# mono_stereo_mixer.net
KiCad netlist of a schematic drawn in EAGLE
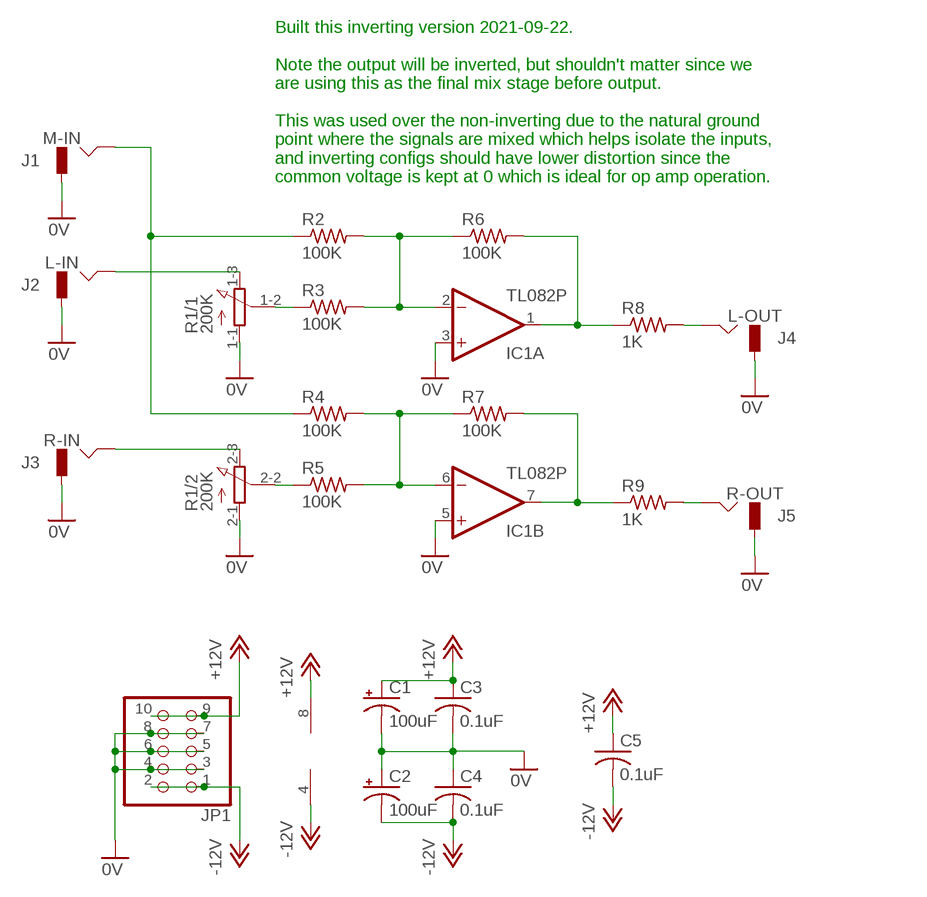
[diagram p0: schematic, sheet 1]

(export (version "E")
  (design (tool "Eeschema 10.0.6"))
  (components
    (comp (ref "C1")
      (value "100uF")
      (footprint "eagle-import:E2-5")
      (libsource (lib "eagle-import") (part "CPOL-USE2-5"))
    )
    (comp (ref "C2")
      (value "100uF")
      (footprint "eagle-import:E2-5")
      (libsource (lib "eagle-import") (part "CPOL-USE2-5"))
    )
    (comp (ref "C3")
      (value "0.1uF")
      (footprint "eagle-import:C025-024X044")
      (libsource (lib "eagle-import") (part "C-US025-024X044"))
    )
    (comp (ref "C4")
      (value "0.1uF")
      (footprint "eagle-import:C025-024X044")
      (libsource (lib "eagle-import") (part "C-US025-024X044"))
    )
    (comp (ref "C5")
      (value "0.1uF")
      (footprint "eagle-import:C025-024X044")
      (libsource (lib "eagle-import") (part "C-US025-024X044"))
    )
    (comp (ref "IC1")
      (value "TL082P")
      (footprint "eagle-import:DIL08")
      (libsource (lib "eagle-import") (part "TL082P"))
    )
    (comp (ref "J1")
      (value "M-IN")
      (footprint "eagle-import:JACK-M")
      (libsource (lib "eagle-import") (part "JACK-M"))
    )
    (comp (ref "J2")
      (value "L-IN")
      (footprint "eagle-import:JACK-M")
      (libsource (lib "eagle-import") (part "JACK-M"))
    )
    (comp (ref "J3")
      (value "R-IN")
      (footprint "eagle-import:JACK-M")
      (libsource (lib "eagle-import") (part "JACK-M"))
    )
    (comp (ref "J4")
      (value "L-OUT")
      (footprint "eagle-import:JACK-M")
      (libsource (lib "eagle-import") (part "JACK-M"))
    )
    (comp (ref "J5")
      (value "R-OUT")
      (footprint "eagle-import:JACK-M")
      (libsource (lib "eagle-import") (part "JACK-M"))
    )
    (comp (ref "JP1")
      (value "PINHD-2X5")
      (footprint "eagle-import:2X05")
      (libsource (lib "eagle-import") (part "PINHD-2X5"))
    )
    (comp (ref "R1")
      (value "200K")
      (footprint "eagle-import:3RP_1610G")
      (libsource (lib "eagle-import") (part "3RP/1610G"))
    )
    (comp (ref "R2")
      (value "100K")
      (footprint "eagle-import:0204_5")
      (libsource (lib "eagle-import") (part "R-US_0204/5"))
    )
    (comp (ref "R3")
      (value "100K")
      (footprint "eagle-import:0204_5")
      (libsource (lib "eagle-import") (part "R-US_0204/5"))
    )
    (comp (ref "R4")
      (value "100K")
      (footprint "eagle-import:0204_5")
      (libsource (lib "eagle-import") (part "R-US_0204/5"))
    )
    (comp (ref "R5")
      (value "100K")
      (footprint "eagle-import:0204_5")
      (libsource (lib "eagle-import") (part "R-US_0204/5"))
    )
    (comp (ref "R6")
      (value "100K")
      (footprint "eagle-import:0204_5")
      (libsource (lib "eagle-import") (part "R-US_0204/5"))
    )
    (comp (ref "R7")
      (value "100K")
      (footprint "eagle-import:0204_5")
      (libsource (lib "eagle-import") (part "R-US_0204/5"))
    )
    (comp (ref "R8")
      (value "1K")
      (footprint "eagle-import:0204_5")
      (libsource (lib "eagle-import") (part "R-US_0204/5"))
    )
    (comp (ref "R9")
      (value "1K")
      (footprint "eagle-import:0204_5")
      (libsource (lib "eagle-import") (part "R-US_0204/5"))
    )
  )
  (nets
    (net (code "1") (name "+12V") (class "Default")
      (node (ref "C1") (pin "+") (pinfunction "+_+") (pintype "passive"))
      (node (ref "C3") (pin "1") (pinfunction "1_1") (pintype "passive"))
      (node (ref "C5") (pin "1") (pinfunction "1_1") (pintype "passive"))
      (node (ref "IC1") (pin "8") (pinfunction "V+_8") (pintype "power_in"))
      (node (ref "JP1") (pin "10") (pinfunction "10_10") (pintype "passive"))
      (node (ref "JP1") (pin "9") (pinfunction "9_9") (pintype "passive"))
    )
    (net (code "2") (name "-12V") (class "Default")
      (node (ref "C2") (pin "-") (pinfunction "-_-") (pintype "passive"))
      (node (ref "C4") (pin "2") (pinfunction "2_2") (pintype "passive"))
      (node (ref "C5") (pin "2") (pinfunction "2_2") (pintype "passive"))
      (node (ref "IC1") (pin "4") (pinfunction "V-_4") (pintype "power_in"))
      (node (ref "JP1") (pin "1") (pinfunction "1_1") (pintype "passive"))
      (node (ref "JP1") (pin "2") (pinfunction "2_2") (pintype "passive"))
    )
    (net (code "3") (name "0V") (class "Default")
      (node (ref "C1") (pin "-") (pinfunction "-_-") (pintype "passive"))
      (node (ref "C2") (pin "+") (pinfunction "+_+") (pintype "passive"))
      (node (ref "C3") (pin "2") (pinfunction "2_2") (pintype "passive"))
      (node (ref "C4") (pin "1") (pinfunction "1_1") (pintype "passive"))
      (node (ref "IC1") (pin "3") (pinfunction "+IN_3") (pintype "input"))
      (node (ref "IC1") (pin "5") (pinfunction "+IN_5") (pintype "input"))
      (node (ref "J1") (pin "GND") (pinfunction "GND_GND") (pintype "bidirectional"))
      (node (ref "J2") (pin "GND") (pinfunction "GND_GND") (pintype "bidirectional"))
      (node (ref "J3") (pin "GND") (pinfunction "GND_GND") (pintype "bidirectional"))
      (node (ref "J4") (pin "GND") (pinfunction "GND_GND") (pintype "bidirectional"))
      (node (ref "J5") (pin "GND") (pinfunction "GND_GND") (pintype "bidirectional"))
      (node (ref "JP1") (pin "3") (pinfunction "3_3") (pintype "passive"))
      (node (ref "JP1") (pin "4") (pinfunction "4_4") (pintype "passive"))
      (node (ref "JP1") (pin "5") (pinfunction "5_5") (pintype "passive"))
      (node (ref "JP1") (pin "6") (pinfunction "6_6") (pintype "passive"))
      (node (ref "JP1") (pin "7") (pinfunction "7_7") (pintype "passive"))
      (node (ref "JP1") (pin "8") (pinfunction "8_8") (pintype "passive"))
      (node (ref "R1") (pin "1-1") (pinfunction "A_1-1") (pintype "passive"))
      (node (ref "R1") (pin "2-1") (pinfunction "A_2-1") (pintype "passive"))
    )
    (net (code "4") (name "Net-(IC1A--IN)") (class "Default")
      (node (ref "IC1") (pin "2") (pinfunction "-IN_2") (pintype "input"))
      (node (ref "R2") (pin "2") (pinfunction "2_2") (pintype "passive"))
      (node (ref "R3") (pin "2") (pinfunction "2_2") (pintype "passive"))
      (node (ref "R6") (pin "1") (pinfunction "1_1") (pintype "passive"))
    )
    (net (code "5") (name "Net-(IC1A-OUT)") (class "Default")
      (node (ref "IC1") (pin "1") (pinfunction "OUT_1") (pintype "output"))
      (node (ref "R6") (pin "2") (pinfunction "2_2") (pintype "passive"))
      (node (ref "R8") (pin "1") (pinfunction "1_1") (pintype "passive"))
    )
    (net (code "6") (name "Net-(IC1B--IN)") (class "Default")
      (node (ref "IC1") (pin "6") (pinfunction "-IN_6") (pintype "input"))
      (node (ref "R4") (pin "2") (pinfunction "2_2") (pintype "passive"))
      (node (ref "R5") (pin "2") (pinfunction "2_2") (pintype "passive"))
      (node (ref "R7") (pin "1") (pinfunction "1_1") (pintype "passive"))
    )
    (net (code "7") (name "Net-(IC1B-OUT)") (class "Default")
      (node (ref "IC1") (pin "7") (pinfunction "OUT_7") (pintype "output"))
      (node (ref "R7") (pin "2") (pinfunction "2_2") (pintype "passive"))
      (node (ref "R9") (pin "1") (pinfunction "1_1") (pintype "passive"))
    )
    (net (code "8") (name "Net-(J1-PadHOT)") (class "Default")
      (node (ref "J1") (pin "HOT") (pinfunction "HOT_HOT") (pintype "bidirectional"))
      (node (ref "R2") (pin "1") (pinfunction "1_1") (pintype "passive"))
      (node (ref "R4") (pin "1") (pinfunction "1_1") (pintype "passive"))
    )
    (net (code "9") (name "Net-(J4-PadHOT)") (class "Default")
      (node (ref "J4") (pin "HOT") (pinfunction "HOT_HOT") (pintype "bidirectional"))
      (node (ref "R8") (pin "2") (pinfunction "2_2") (pintype "passive"))
    )
    (net (code "10") (name "Net-(J5-PadHOT)") (class "Default")
      (node (ref "J5") (pin "HOT") (pinfunction "HOT_HOT") (pintype "bidirectional"))
      (node (ref "R9") (pin "2") (pinfunction "2_2") (pintype "passive"))
    )
    (net (code "11") (name "Net-(R1A-E)") (class "Default")
      (node (ref "J2") (pin "HOT") (pinfunction "HOT_HOT") (pintype "bidirectional"))
      (node (ref "R1") (pin "1-3") (pinfunction "E_1-3") (pintype "passive"))
    )
    (net (code "12") (name "Net-(R1A-S)") (class "Default")
      (node (ref "R1") (pin "1-2") (pinfunction "S_1-2") (pintype "passive"))
      (node (ref "R3") (pin "1") (pinfunction "1_1") (pintype "passive"))
    )
    (net (code "13") (name "Net-(R1B-E)") (class "Default")
      (node (ref "J3") (pin "HOT") (pinfunction "HOT_HOT") (pintype "bidirectional"))
      (node (ref "R1") (pin "2-3") (pinfunction "E_2-3") (pintype "passive"))
    )
    (net (code "14") (name "Net-(R1B-S)") (class "Default")
      (node (ref "R1") (pin "2-2") (pinfunction "S_2-2") (pintype "passive"))
      (node (ref "R5") (pin "1") (pinfunction "1_1") (pintype "passive"))
    )
  )
)
